# 100068622_rail_discharge.net
KiCad netlist of a schematic drawn in Altium Designer
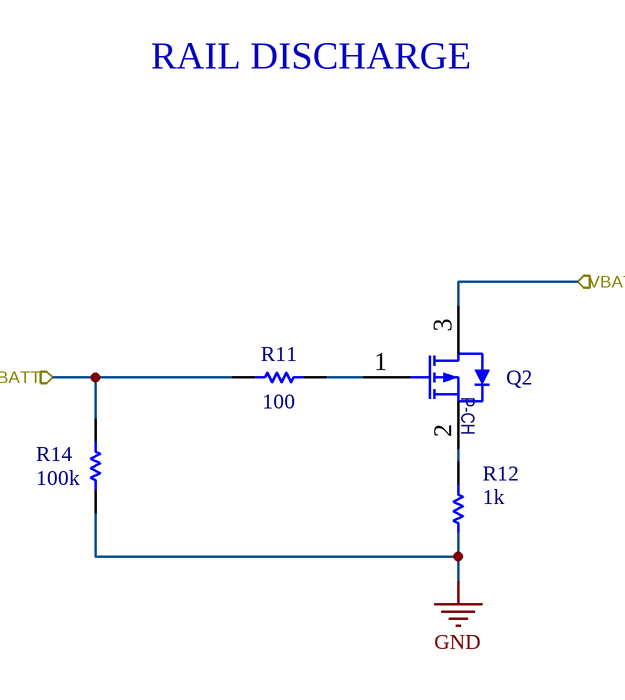
[diagram p0: 100068622_rail_discharge.SchDoc]

(export (version "E")
  (design (tool "Eeschema 10.0.6"))
  (components
    (comp (ref "Q2")
      (value "DMP610DL-13")
      (footprint "IC-SOT23-3-A")
      (description "Trans Mosfet P-ch 60V 0.18A 3-PIN SOT-23 T/r")
      (libsource (lib "Picatinny Server") (part "Mosfet P-Channel Single"))
    )
    (comp (ref "R11")
      (value "100")
      (footprint "RES-0402-B")
      (description "Res 0402 100 Ohm 0.1W 1% Thick Film")
      (fields (field (name "POWER") "100mW") (field (name "TOLERANCE") "1%"))
      (libsource (lib "Picatinny Server") (part "Resistor"))
    )
    (comp (ref "R12")
      (value "1k")
      (footprint "RES-2512-C")
      (description "Res Thick Film 2512 1K Ohm 1% 1W ±100ppm/C Pad SMD T/R Automotive AEC-Q200")
      (fields (field (name "Comment") "Resistor"))
      (libsource (lib "Picatinny Server") (part "Resistor"))
    )
    (comp (ref "R14")
      (value "100k")
      (footprint "RES-0402-C")
      (description "Res 0402 100K 1/10W 1% Thick Flim")
      (fields (field (name "TOLERANCE") "1%"))
      (libsource (lib "Picatinny Server") (part "Resistor"))
    )
  )
  (nets
    (net (code "1") (name "/VBATT") (class "Default")
      (node (ref "R11") (pin "2") (pinfunction "2_2") (pintype "passive"))
      (node (ref "R14") (pin "2") (pinfunction "2_2") (pintype "passive"))
    )
    (net (code "2") (name "/VBATT_PROT") (class "Default")
      (node (ref "Q2") (pin "3") (pinfunction "D_3") (pintype "passive"))
    )
    (net (code "3") (name "GND") (class "Default")
      (node (ref "R12") (pin "1") (pinfunction "1_1") (pintype "passive"))
      (node (ref "R14") (pin "1") (pinfunction "1_1") (pintype "passive"))
    )
    (net (code "4") (name "Net-(Q2-G)") (class "Default")
      (node (ref "Q2") (pin "1") (pinfunction "G_1") (pintype "passive"))
      (node (ref "R11") (pin "1") (pinfunction "1_1") (pintype "passive"))
    )
    (net (code "5") (name "Net-(Q2-S)") (class "Default")
      (node (ref "Q2") (pin "2") (pinfunction "S_2") (pintype "passive"))
      (node (ref "R12") (pin "2") (pinfunction "2_2") (pintype "passive"))
    )
  )
)
